# USB_PD.net
KiCad netlist of a schematic drawn in Altium Designer
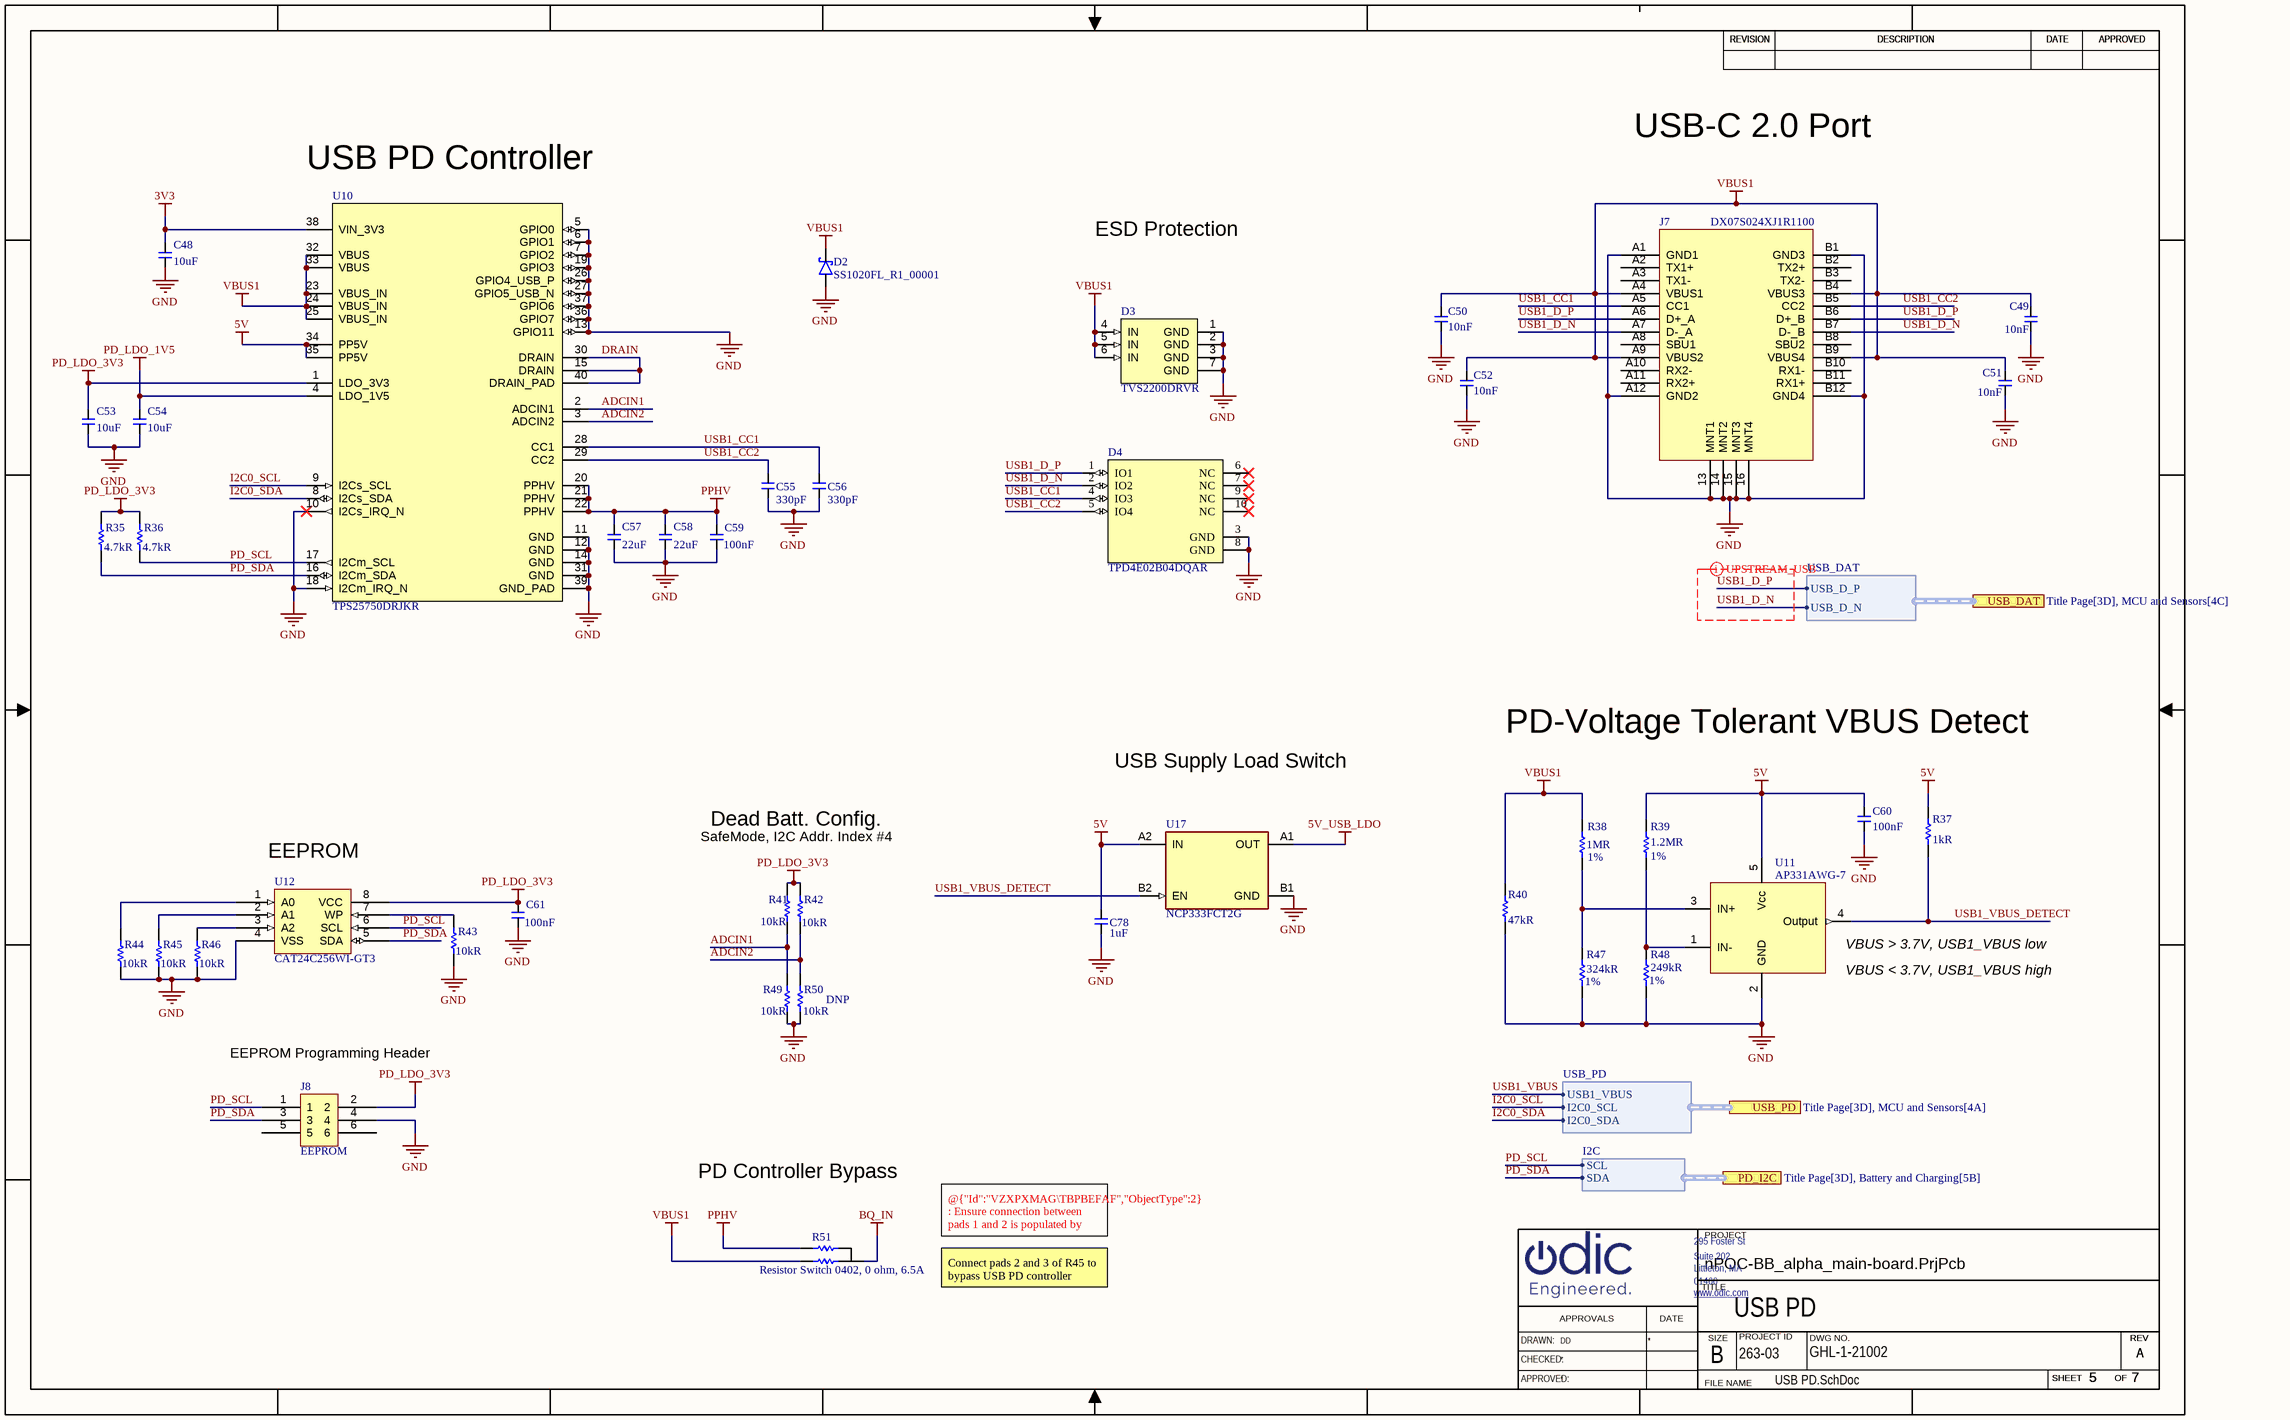
[diagram p0: USB PD.SchDoc]

(export (version "E")
  (design (tool "Eeschema 10.0.6"))
  (components
    (comp (ref "C48")
      (value "C0402_10u_10V_20pct")
      (footprint "C0402")
      (description "Ceramic capacitor SMD; 0402; 10uF; 10V; X5R; 20%")
      (fields (field (name "CAPACITANCE") "10uF") (field (name "TOLERANCE") "20%"))
      (libsource (lib "Odic Inc") (part "cAP"))
    )
    (comp (ref "C49")
      (value "10nF")
      (footprint "C0402")
      (description "Multilayer Ceramic Capacitor, 0.01 uF, 35 V, ± 10%, X7R, 0402 [1005 Metric]")
      (fields (field (name "TOLERANCE") "10%") (field (name "Comment") "C0402_10n_35V_10pct"))
      (libsource (lib "Odic Inc") (part "cAP"))
    )
    (comp (ref "C50")
      (value "10nF")
      (footprint "C0402")
      (description "Multilayer Ceramic Capacitor, 0.01 uF, 35 V, ± 10%, X7R, 0402 [1005 Metric]")
      (fields (field (name "TOLERANCE") "10%") (field (name "Comment") "C0402_10n_35V_10pct"))
      (libsource (lib "Odic Inc") (part "cAP"))
    )
    (comp (ref "C51")
      (value "10nF")
      (footprint "C0402")
      (description "Multilayer Ceramic Capacitor, 0.01 uF, 35 V, ± 10%, X7R, 0402 [1005 Metric]")
      (fields (field (name "TOLERANCE") "10%") (field (name "Comment") "C0402_10n_35V_10pct"))
      (libsource (lib "Odic Inc") (part "cAP"))
    )
    (comp (ref "C52")
      (value "10nF")
      (footprint "C0402")
      (description "Multilayer Ceramic Capacitor, 0.01 uF, 35 V, ± 10%, X7R, 0402 [1005 Metric]")
      (fields (field (name "TOLERANCE") "10%") (field (name "Comment") "C0402_10n_35V_10pct"))
      (libsource (lib "Odic Inc") (part "cAP"))
    )
    (comp (ref "C53")
      (value "C0402_10u_10V_20pct")
      (footprint "C0402")
      (description "Ceramic capacitor SMD; 0402; 10uF; 10V; X5R; 20%")
      (fields (field (name "CAPACITANCE") "10uF") (field (name "TOLERANCE") "20%"))
      (libsource (lib "Odic Inc") (part "cAP"))
    )
    (comp (ref "C54")
      (value "C0402_10u_10V_20pct")
      (footprint "C0402")
      (description "Ceramic capacitor SMD; 0402; 10uF; 10V; X5R; 20%")
      (fields (field (name "CAPACITANCE") "10uF") (field (name "TOLERANCE") "20%"))
      (libsource (lib "Odic Inc") (part "cAP"))
    )
    (comp (ref "C55")
      (value "330pF")
      (footprint "C0402")
      (description "0402 330 pF 50 V ±5% Tolerance C0G SMT Multilayer Ceramic Capacitor")
      (fields (field (name "VOLTAGE") "50V") (field (name "TOLERANCE") "5%"))
      (libsource (lib "Odic Inc") (part "cAP"))
    )
    (comp (ref "C56")
      (value "330pF")
      (footprint "C0402")
      (description "0402 330 pF 50 V ±5% Tolerance C0G SMT Multilayer Ceramic Capacitor")
      (fields (field (name "VOLTAGE") "50V") (field (name "TOLERANCE") "5%"))
      (libsource (lib "Odic Inc") (part "cAP"))
    )
    (comp (ref "C57")
      (value "C0805_22u_25V_20pct")
      (footprint "c0805")
      (description "Multilayer Ceramic Capacitor, 22 uF, 25 V, ± 20%, X5R, 0805 [2012 Metric]")
      (fields (field (name "CAPACITANCE") "22uF"))
      (libsource (lib "Odic Inc") (part "cAP"))
    )
    (comp (ref "C58")
      (value "C0805_22u_25V_20pct")
      (footprint "c0805")
      (description "Multilayer Ceramic Capacitor, 22 uF, 25 V, ± 20%, X5R, 0805 [2012 Metric]")
      (fields (field (name "CAPACITANCE") "22uF"))
      (libsource (lib "Odic Inc") (part "cAP"))
    )
    (comp (ref "C59")
      (value "C0402_0u1_25V_10pct")
      (footprint "C0402")
      (description "Cap Ceramic 0.1uF 25V X5R 10% Pad SMD 0402 Multi Layer Ceramic Capacitor (MLCC)")
      (fields
        (field (name "VOLTAGE") "25V")
        (field (name "TOLERANCE") "10%")
        (field (name "CAPACITANCE") "100nF")
      )
      (libsource (lib "Odic Inc") (part "cAP"))
    )
    (comp (ref "C60")
      (value "C0402_100n_16V_10pct")
      (footprint "C0402")
      (description "0.1 µF ±10% 16V Ceramic Capacitor X7R 0402 (1005 Metric)")
      (fields
        (field (name "VOLTAGE") "16V")
        (field (name "TOLERANCE") "10%")
        (field (name "CAPACITANCE") "100nF")
      )
      (libsource (lib "Odic Inc") (part "cAP"))
    )
    (comp (ref "C61")
      (value "C0402_0u1_25V_10pct")
      (footprint "C0402")
      (description "Cap Ceramic 0.1uF 25V X5R 10% Pad SMD 0402 Multi Layer Ceramic Capacitor (MLCC)")
      (fields
        (field (name "VOLTAGE") "25V")
        (field (name "TOLERANCE") "10%")
        (field (name "CAPACITANCE") "100nF")
      )
      (libsource (lib "Odic Inc") (part "cAP"))
    )
    (comp (ref "C78")
      (value "C0402_1u_6V3_10pct")
      (footprint "C0402")
      (description "Cap Ceramic 1uF 6.3V X5R 10% SMD 0402 85C Paper T/R")
      (fields (field (name "CAPACITANCE") "1uF") (field (name "TOLERANCE") "10%"))
      (libsource (lib "Odic Inc") (part "cAP"))
    )
    (comp (ref "D2")
      (value "SS1020FL_R1_00001")
      (footprint "sod-123fl_AK")
      (description "Diode Schottky 20V 1A 2-Pin SOD-123FL T/R")
      (libsource (lib "Odic Inc") (part "Schottky"))
    )
    (comp (ref "D3")
      (value "TVS2200DRVR")
      (footprint "dfn7_2x2_p65mm")
      (description "22-V flat-clamp surge protection device 6-WSON -40 to 125")
      (libsource (lib "Odic Inc") (part "TVS2200DRVR-sym"))
    )
    (comp (ref "D4")
      (value "TPD4E02B04DQAR")
      (footprint "dfn10_1p1x2p6_p5mm")
      (description "Quad 0.25-pF, ±3.6-V, ±12-kV ESD protection diode for USB 3.0, HDMI 2.0 & High Speed Signals")
      (libsource (lib "Odic Inc") (part "TPD4E02B04DQAR-sym"))
    )
    (comp (ref "J7")
      (value "DX07S024XJ1R1100")
      (footprint "USB_JAE_DX07S024XJ1R1100")
      (libsource (lib "Odic Inc") (part "DX07S024XJ1R1100-symbol-1"))
    )
    (comp (ref "J8")
      (value "EEPROM")
      (footprint "tc2030-mcp-nl")
      (description "6 Pin Tag-Connect Header Footprint. Pads.")
      (libsource (lib "Odic Inc") (part "TC2030-FP-Symbol-1"))
    )
    (comp (ref "R35")
      (value "R0402_4k7_1pct")
      (footprint "R0402")
      (description "RES 4.7K OHM 1% 1/16W 0402")
      (fields (field (name "TOLERANCE") "1%") (field (name "RESISTANCE") "4.7kR"))
      (libsource (lib "Odic Inc") (part "RES"))
    )
    (comp (ref "R36")
      (value "R0402_4k7_1pct")
      (footprint "R0402")
      (description "RES 4.7K OHM 1% 1/16W 0402")
      (fields (field (name "TOLERANCE") "1%") (field (name "RESISTANCE") "4.7kR"))
      (libsource (lib "Odic Inc") (part "RES"))
    )
    (comp (ref "R37")
      (value "R0402_1k0_1pct")
      (footprint "R0402")
      (description "Surface Mount Chip Resistor, Thick Film, RC Series, 1 kohm, 62.5 mW, 1%, 50 V, 0402 [1005 Metric]")
      (fields (field (name "RESISTANCE") "1kR") (field (name "TOLERANCE") "1%"))
      (libsource (lib "Odic Inc") (part "RES"))
    )
    (comp (ref "R38")
      (value "1MR")
      (footprint "R0402")
      (description "Res Thick Film 0402 1M Ohm 1% 0.063W(1/16W) ±100ppm/C Pad SMD T/R")
      (fields (field (name "TOLERANCE") "1%") (field (name "Comment") "R0402_1M_1pct"))
      (libsource (lib "Odic Inc") (part "RES"))
    )
    (comp (ref "R39")
      (value "R0402_1M2_1pct")
      (footprint "R0402")
      (description "Res Thick Film 0402 1.2M Ohm 1% 0.063W(1/16W) ±100ppm/C Pad SMD Automotive T/R")
      (fields (field (name "RESISTANCE") "1.2MR") (field (name "TOLERANCE") "1%"))
      (libsource (lib "Odic Inc") (part "RES"))
    )
    (comp (ref "R40")
      (value "R0402_47k_1pct")
      (footprint "R0402")
      (description "Res General Purpose Thick Film 0402 47K Ohm 1% 1/16W ±100ppm/°C Molded SMD Paper T/R")
      (fields (field (name "TOLERANCE") "1%") (field (name "RESISTANCE") "47kR"))
      (libsource (lib "Odic Inc") (part "RES"))
    )
    (comp (ref "R41")
      (value "R0402_10k_1pct")
      (footprint "R0402")
      (description "Res Thick Film 0402 10K Ohm 1% 1/16W ±100ppm/°C Molded SMD SMD T/R")
      (fields (field (name "RESISTANCE") "10kR") (field (name "TOLERANCE") "1%"))
      (libsource (lib "Odic Inc") (part "RES"))
    )
    (comp (ref "R42")
      (value "R0402_10k_1pct")
      (footprint "R0402")
      (description "Res Thick Film 0402 10K Ohm 1% 1/16W ±100ppm/°C Molded SMD SMD T/R")
      (fields (field (name "RESISTANCE") "10kR") (field (name "TOLERANCE") "1%"))
      (libsource (lib "Odic Inc") (part "RES"))
    )
    (comp (ref "R43")
      (value "R0402_10k_1pct")
      (footprint "R0402")
      (description "Res Thick Film 0402 10K Ohm 1% 1/16W ±100ppm/°C Molded SMD SMD T/R")
      (fields (field (name "RESISTANCE") "10kR") (field (name "TOLERANCE") "1%"))
      (libsource (lib "Odic Inc") (part "RES"))
    )
    (comp (ref "R44")
      (value "R0402_10k_1pct")
      (footprint "R0402")
      (description "Res Thick Film 0402 10K Ohm 1% 1/16W ±100ppm/°C Molded SMD SMD T/R")
      (fields (field (name "RESISTANCE") "10kR") (field (name "TOLERANCE") "1%"))
      (libsource (lib "Odic Inc") (part "RES"))
    )
    (comp (ref "R45")
      (value "R0402_10k_1pct")
      (footprint "R0402")
      (description "Res Thick Film 0402 10K Ohm 1% 1/16W ±100ppm/°C Molded SMD SMD T/R")
      (fields (field (name "RESISTANCE") "10kR") (field (name "TOLERANCE") "1%"))
      (libsource (lib "Odic Inc") (part "RES"))
    )
    (comp (ref "R46")
      (value "R0402_10k_1pct")
      (footprint "R0402")
      (description "Res Thick Film 0402 10K Ohm 1% 1/16W ±100ppm/°C Molded SMD SMD T/R")
      (fields (field (name "RESISTANCE") "10kR") (field (name "TOLERANCE") "1%"))
      (libsource (lib "Odic Inc") (part "RES"))
    )
    (comp (ref "R47")
      (value "324kR")
      (footprint "R0402")
      (description "SMD Chip Resistor, 324 kOhm, ± 1%, 63 mW, 0402 [1005 Metric], Thick Film, General Purpose")
      (fields (field (name "TOLERANCE") "1%") (field (name "Comment") "R0402_324k_1pct"))
      (libsource (lib "Odic Inc") (part "RES"))
    )
    (comp (ref "R48")
      (value "R0402_249k_1pct")
      (footprint "R0402")
      (description "Res Thick Film 0402 249K Ohm 1% 0.063W ±100ppm/°C Molded SMD Paper T/R")
      (fields (field (name "TOLERANCE") "1%") (field (name "RESISTANCE") "249kR"))
      (libsource (lib "Odic Inc") (part "RES"))
    )
    (comp (ref "R49")
      (value "R0402_10k_1pct")
      (footprint "R0402")
      (description "Res Thick Film 0402 10K Ohm 1% 1/16W ±100ppm/°C Molded SMD SMD T/R")
      (fields (field (name "RESISTANCE") "10kR") (field (name "TOLERANCE") "1%"))
      (libsource (lib "Odic Inc") (part "RES"))
    )
    (comp (ref "R50")
      (value "R0402_10k_1pct")
      (footprint "R0402")
      (description "Res Thick Film 0402 10K Ohm 1% 1/16W ±100ppm/°C Molded SMD SMD T/R")
      (fields
        (field (name "RESISTANCE") "10kR")
        (field (name "TOLERANCE") "1%")
        (field (name "INSTALL") "DNP")
      )
      (libsource (lib "Odic Inc") (part "RES"))
    )
    (comp (ref "R51")
      (value "Resistor Switch 0402, 0 ohm, 6.5A")
      (footprint "r0402x2")
      (fields (field (name "TOLERANCE") "5%"))
      (libsource (lib "Odic Inc") (part "RES_SWITCH"))
    )
    (comp (ref "U10")
      (value "TPS25750DRJKR")
      (footprint "qfn40_6x4_p4mm-RJK0038B")
      (description "Highly integrated USB Type-C® and USB PD controller with pre-configured GUI 38-WQFN -40 to 125")
      (libsource (lib "Odic Inc") (part "TPS25750DRJKR-Symbol-1"))
    )
    (comp (ref "U11")
      (value "AP331AWG-7")
      (footprint "SOT25")
      (description "IC COMPARATOR SGL DIFF SOT-25")
      (libsource (lib "Odic Inc") (part "84157f6d693ce6938d681314262b7f3"))
    )
    (comp (ref "U12")
      (value "CAT24C256WI-GT3")
      (footprint "SO8")
      (description "IC EEPROM 256KBIT 400KHZ 8SOIC")
      (libsource (lib "Odic Inc") (part "CAT24C256WI-GT3-Symbol-1"))
    )
    (comp (ref "U17")
      (value "NCP333FCT2G")
      (footprint "bga4_p743xp743_p4mm")
      (description "IC LOAD SWITCH W/DIS 1.5A 4WLCSP")
      (libsource (lib "Odic Inc") (part "97019fd276bc7644be76e1f711e9589"))
    )
  )
  (nets
    (net (code "4") (name "/ADCIN1") (class "Default")
      (node (ref "R41") (pin "1") (pinfunction "1_1") (pintype "passive"))
      (node (ref "R49") (pin "2") (pinfunction "2_2") (pintype "passive"))
      (node (ref "U10") (pin "2") (pinfunction "ADCIN1_2") (pintype "passive"))
    )
    (net (code "5") (name "/ADCIN2") (class "Default")
      (node (ref "R42") (pin "1") (pinfunction "1_1") (pintype "passive"))
      (node (ref "R50") (pin "2") (pinfunction "2_2") (pintype "passive"))
      (node (ref "U10") (pin "3") (pinfunction "ADCIN2_3") (pintype "passive"))
    )
    (net (code "6") (name "/DRAIN") (class "Default")
      (node (ref "U10") (pin "15") (pinfunction "DRAIN_15") (pintype "passive"))
      (node (ref "U10") (pin "30") (pinfunction "DRAIN_30") (pintype "passive"))
      (node (ref "U10") (pin "40") (pinfunction "DRAIN_PAD_40") (pintype "passive"))
    )
    (net (code "7") (name "/I2C0_SCL") (class "Default")
      (node (ref "U10") (pin "9") (pinfunction "I2Cs_SCL_9") (pintype "input"))
    )
    (net (code "8") (name "/I2C0_SDA") (class "Default")
      (node (ref "U10") (pin "8") (pinfunction "I2Cs_SDA_8") (pintype "bidirectional"))
    )
    (net (code "9") (name "/PD_SCL") (class "Default")
      (node (ref "J8") (pin "1") (pinfunction "1_1") (pintype "passive"))
      (node (ref "R36") (pin "1") (pinfunction "1_1") (pintype "passive"))
      (node (ref "U10") (pin "17") (pinfunction "I2Cm_SCL_17") (pintype "output"))
      (node (ref "U12") (pin "6") (pinfunction "SCL_6") (pintype "input"))
    )
    (net (code "10") (name "/PD_SDA") (class "Default")
      (node (ref "J8") (pin "3") (pinfunction "3_3") (pintype "passive"))
      (node (ref "R35") (pin "1") (pinfunction "1_1") (pintype "passive"))
      (node (ref "U10") (pin "16") (pinfunction "I2Cm_SDA_16") (pintype "bidirectional"))
      (node (ref "U12") (pin "5") (pinfunction "SDA_5") (pintype "bidirectional"))
    )
    (net (code "11") (name "/USB1_CC1") (class "Default")
      (node (ref "C56") (pin "2") (pinfunction "2_2") (pintype "passive"))
      (node (ref "D4") (pin "4") (pinfunction "IO3_4") (pintype "bidirectional"))
      (node (ref "J7") (pin "A5") (pinfunction "CC1_A5") (pintype "passive"))
      (node (ref "U10") (pin "28") (pinfunction "CC1_28") (pintype "passive"))
    )
    (net (code "12") (name "/USB1_CC2") (class "Default")
      (node (ref "C55") (pin "2") (pinfunction "2_2") (pintype "passive"))
      (node (ref "D4") (pin "5") (pinfunction "IO4_5") (pintype "bidirectional"))
      (node (ref "J7") (pin "B5") (pinfunction "CC2_B5") (pintype "passive"))
      (node (ref "U10") (pin "29") (pinfunction "CC2_29") (pintype "passive"))
    )
    (net (code "13") (name "/USB1_D_N") (class "Default")
      (node (ref "D4") (pin "2") (pinfunction "IO2_2") (pintype "bidirectional"))
      (node (ref "J7") (pin "A7") (pinfunction "D-_A_A7") (pintype "passive"))
      (node (ref "J7") (pin "B7") (pinfunction "D-_B_B7") (pintype "passive"))
    )
    (net (code "14") (name "/USB1_D_P") (class "Default")
      (node (ref "D4") (pin "1") (pinfunction "IO1_1") (pintype "bidirectional"))
      (node (ref "J7") (pin "A6") (pinfunction "D+_A_A6") (pintype "passive"))
      (node (ref "J7") (pin "B6") (pinfunction "D+_B_B6") (pintype "passive"))
    )
    (net (code "16") (name "/USB1_VBUS_DETECT") (class "Default")
      (node (ref "R37") (pin "1") (pinfunction "1_1") (pintype "passive"))
      (node (ref "U11") (pin "4") (pinfunction "Output_4") (pintype "output"))
      (node (ref "U17") (pin "B2") (pinfunction "EN_B2") (pintype "input"))
    )
    (net (code "20") (name "3V3") (class "Default")
      (node (ref "C48") (pin "2") (pinfunction "2_2") (pintype "passive"))
      (node (ref "U10") (pin "38") (pinfunction "VIN_3V3_38") (pintype "power_in"))
    )
    (net (code "21") (name "5V") (class "Default")
      (node (ref "C60") (pin "2") (pinfunction "2_2") (pintype "passive"))
      (node (ref "C78") (pin "2") (pinfunction "2_2") (pintype "passive"))
      (node (ref "R37") (pin "2") (pinfunction "2_2") (pintype "passive"))
      (node (ref "R39") (pin "2") (pinfunction "2_2") (pintype "passive"))
      (node (ref "U10") (pin "34") (pinfunction "PP5V_34") (pintype "power_in"))
      (node (ref "U10") (pin "35") (pinfunction "PP5V_35") (pintype "power_in"))
      (node (ref "U11") (pin "5") (pinfunction "Vcc_5") (pintype "power_in"))
      (node (ref "U17") (pin "A2") (pinfunction "IN_A2") (pintype "power_in"))
    )
    (net (code "22") (name "5V_USB_LDO") (class "Default")
      (node (ref "U17") (pin "A1") (pinfunction "OUT_A1") (pintype "power_in"))
    )
    (net (code "23") (name "BQ_IN") (class "Default")
      (node (ref "R51") (pin "2") (pinfunction "2_2") (pintype "passive"))
    )
    (net (code "24") (name "GND") (class "Default")
      (node (ref "C48") (pin "1") (pinfunction "1_1") (pintype "passive"))
      (node (ref "C49") (pin "1") (pinfunction "1_1") (pintype "passive"))
      (node (ref "C50") (pin "1") (pinfunction "1_1") (pintype "passive"))
      (node (ref "C51") (pin "1") (pinfunction "1_1") (pintype "passive"))
      (node (ref "C52") (pin "1") (pinfunction "1_1") (pintype "passive"))
      (node (ref "C53") (pin "1") (pinfunction "1_1") (pintype "passive"))
      (node (ref "C54") (pin "1") (pinfunction "1_1") (pintype "passive"))
      (node (ref "C55") (pin "1") (pinfunction "1_1") (pintype "passive"))
      (node (ref "C56") (pin "1") (pinfunction "1_1") (pintype "passive"))
      (node (ref "C57") (pin "1") (pinfunction "1_1") (pintype "passive"))
      (node (ref "C58") (pin "1") (pinfunction "1_1") (pintype "passive"))
      (node (ref "C59") (pin "1") (pinfunction "1_1") (pintype "passive"))
      (node (ref "C60") (pin "1") (pinfunction "1_1") (pintype "passive"))
      (node (ref "C61") (pin "1") (pinfunction "1_1") (pintype "passive"))
      (node (ref "C78") (pin "1") (pinfunction "1_1") (pintype "passive"))
      (node (ref "D2") (pin "A") (pinfunction "A_A") (pintype "passive"))
      (node (ref "D3") (pin "1") (pinfunction "GND_1") (pintype "power_in"))
      (node (ref "D3") (pin "2") (pinfunction "GND_2") (pintype "power_in"))
      (node (ref "D3") (pin "3") (pinfunction "GND_3") (pintype "power_in"))
      (node (ref "D3") (pin "7") (pinfunction "GND_7") (pintype "power_in"))
      (node (ref "D4") (pin "3") (pinfunction "GND_3") (pintype "power_in"))
      (node (ref "D4") (pin "8") (pinfunction "GND_8") (pintype "power_in"))
      (node (ref "J7") (pin "13") (pinfunction "MNT1_13") (pintype "passive"))
      (node (ref "J7") (pin "14") (pinfunction "MNT2_14") (pintype "passive"))
      (node (ref "J7") (pin "15") (pinfunction "MNT3_15") (pintype "passive"))
      (node (ref "J7") (pin "16") (pinfunction "MNT4_16") (pintype "passive"))
      (node (ref "J7") (pin "A1") (pinfunction "GND1_A1") (pintype "passive"))
      (node (ref "J7") (pin "A12") (pinfunction "GND2_A12") (pintype "passive"))
      (node (ref "J7") (pin "B1") (pinfunction "GND3_B1") (pintype "passive"))
      (node (ref "J7") (pin "B12") (pinfunction "GND4_B12") (pintype "passive"))
      (node (ref "J8") (pin "4") (pinfunction "4_4") (pintype "passive"))
      (node (ref "R40") (pin "1") (pinfunction "1_1") (pintype "passive"))
      (node (ref "R43") (pin "1") (pinfunction "1_1") (pintype "passive"))
      (node (ref "R44") (pin "1") (pinfunction "1_1") (pintype "passive"))
      (node (ref "R45") (pin "1") (pinfunction "1_1") (pintype "passive"))
      (node (ref "R46") (pin "1") (pinfunction "1_1") (pintype "passive"))
      (node (ref "R47") (pin "1") (pinfunction "1_1") (pintype "passive"))
      (node (ref "R48") (pin "1") (pinfunction "1_1") (pintype "passive"))
      (node (ref "R49") (pin "1") (pinfunction "1_1") (pintype "passive"))
      (node (ref "R50") (pin "1") (pinfunction "1_1") (pintype "passive"))
      (node (ref "U10") (pin "10") (pinfunction "I2Cs_IRQ_N_10") (pintype "output"))
      (node (ref "U10") (pin "11") (pinfunction "GND_11") (pintype "power_in"))
      (node (ref "U10") (pin "12") (pinfunction "GND_12") (pintype "power_in"))
      (node (ref "U10") (pin "13") (pinfunction "GPIO11_13") (pintype "bidirectional"))
      (node (ref "U10") (pin "14") (pinfunction "GND_14") (pintype "power_in"))
      (node (ref "U10") (pin "18") (pinfunction "I2Cm_IRQ_N_18") (pintype "input"))
      (node (ref "U10") (pin "19") (pinfunction "GPIO3_19") (pintype "bidirectional"))
      (node (ref "U10") (pin "26") (pinfunction "GPIO4_USB_P_26") (pintype "bidirectional"))
      (node (ref "U10") (pin "27") (pinfunction "GPIO5_USB_N_27") (pintype "bidirectional"))
      (node (ref "U10") (pin "31") (pinfunction "GND_31") (pintype "power_in"))
      (node (ref "U10") (pin "36") (pinfunction "GPIO7_36") (pintype "bidirectional"))
      (node (ref "U10") (pin "37") (pinfunction "GPIO6_37") (pintype "bidirectional"))
      (node (ref "U10") (pin "39") (pinfunction "GND_PAD_39") (pintype "power_in"))
      (node (ref "U10") (pin "5") (pinfunction "GPIO0_5") (pintype "bidirectional"))
      (node (ref "U10") (pin "6") (pinfunction "GPIO1_6") (pintype "bidirectional"))
      (node (ref "U10") (pin "7") (pinfunction "GPIO2_7") (pintype "bidirectional"))
      (node (ref "U11") (pin "2") (pinfunction "GND_2") (pintype "power_in"))
      (node (ref "U12") (pin "4") (pinfunction "VSS_4") (pintype "passive"))
      (node (ref "U17") (pin "B1") (pinfunction "GND_B1") (pintype "power_in"))
    )
    (net (code "25") (name "Net-(U11-IN+)") (class "Default")
      (node (ref "R38") (pin "1") (pinfunction "1_1") (pintype "passive"))
      (node (ref "R47") (pin "2") (pinfunction "2_2") (pintype "passive"))
      (node (ref "U11") (pin "3") (pinfunction "IN+_3") (pintype "tri_state"))
    )
    (net (code "26") (name "Net-(U11-IN-)") (class "Default")
      (node (ref "R39") (pin "1") (pinfunction "1_1") (pintype "passive"))
      (node (ref "R48") (pin "2") (pinfunction "2_2") (pintype "passive"))
      (node (ref "U11") (pin "1") (pinfunction "IN-_1") (pintype "tri_state"))
    )
    (net (code "27") (name "Net-(U12-A0)") (class "Default")
      (node (ref "R44") (pin "2") (pinfunction "2_2") (pintype "passive"))
      (node (ref "U12") (pin "1") (pinfunction "A0_1") (pintype "input"))
    )
    (net (code "28") (name "Net-(U12-A1)") (class "Default")
      (node (ref "R45") (pin "2") (pinfunction "2_2") (pintype "passive"))
      (node (ref "U12") (pin "2") (pinfunction "A1_2") (pintype "input"))
    )
    (net (code "29") (name "Net-(U12-A2)") (class "Default")
      (node (ref "R46") (pin "2") (pinfunction "2_2") (pintype "passive"))
      (node (ref "U12") (pin "3") (pinfunction "A2_3") (pintype "input"))
    )
    (net (code "30") (name "Net-(U12-WP)") (class "Default")
      (node (ref "R43") (pin "2") (pinfunction "2_2") (pintype "passive"))
      (node (ref "U12") (pin "7") (pinfunction "WP_7") (pintype "input"))
    )
    (net (code "31") (name "PD_LDO_1V5") (class "Default")
      (node (ref "C54") (pin "2") (pinfunction "2_2") (pintype "passive"))
      (node (ref "U10") (pin "4") (pinfunction "LDO_1V5_4") (pintype "passive"))
    )
    (net (code "32") (name "PD_LDO_3V3") (class "Default")
      (node (ref "C53") (pin "2") (pinfunction "2_2") (pintype "passive"))
      (node (ref "C61") (pin "2") (pinfunction "2_2") (pintype "passive"))
      (node (ref "J8") (pin "2") (pinfunction "2_2") (pintype "passive"))
      (node (ref "R35") (pin "2") (pinfunction "2_2") (pintype "passive"))
      (node (ref "R36") (pin "2") (pinfunction "2_2") (pintype "passive"))
      (node (ref "R41") (pin "2") (pinfunction "2_2") (pintype "passive"))
      (node (ref "R42") (pin "2") (pinfunction "2_2") (pintype "passive"))
      (node (ref "U10") (pin "1") (pinfunction "LDO_3V3_1") (pintype "passive"))
      (node (ref "U12") (pin "8") (pinfunction "VCC_8") (pintype "passive"))
    )
    (net (code "33") (name "PPHV") (class "Default")
      (node (ref "C57") (pin "2") (pinfunction "2_2") (pintype "passive"))
      (node (ref "C58") (pin "2") (pinfunction "2_2") (pintype "passive"))
      (node (ref "C59") (pin "2") (pinfunction "2_2") (pintype "passive"))
      (node (ref "R51") (pin "1") (pinfunction "1_1") (pintype "passive"))
      (node (ref "U10") (pin "20") (pinfunction "PPHV_20") (pintype "passive"))
      (node (ref "U10") (pin "21") (pinfunction "PPHV_21") (pintype "passive"))
      (node (ref "U10") (pin "22") (pinfunction "PPHV_22") (pintype "passive"))
    )
    (net (code "34") (name "VBUS1") (class "Default")
      (node (ref "C49") (pin "2") (pinfunction "2_2") (pintype "passive"))
      (node (ref "C50") (pin "2") (pinfunction "2_2") (pintype "passive"))
      (node (ref "C51") (pin "2") (pinfunction "2_2") (pintype "passive"))
      (node (ref "C52") (pin "2") (pinfunction "2_2") (pintype "passive"))
      (node (ref "D2") (pin "K") (pinfunction "K_K") (pintype "passive"))
      (node (ref "D3") (pin "4") (pinfunction "IN_4") (pintype "input"))
      (node (ref "D3") (pin "5") (pinfunction "IN_5") (pintype "input"))
      (node (ref "D3") (pin "6") (pinfunction "IN_6") (pintype "input"))
      (node (ref "J7") (pin "A4") (pinfunction "VBUS1_A4") (pintype "passive"))
      (node (ref "J7") (pin "A9") (pinfunction "VBUS2_A9") (pintype "passive"))
      (node (ref "J7") (pin "B4") (pinfunction "VBUS3_B4") (pintype "passive"))
      (node (ref "J7") (pin "B9") (pinfunction "VBUS4_B9") (pintype "passive"))
      (node (ref "R38") (pin "2") (pinfunction "2_2") (pintype "passive"))
      (node (ref "R40") (pin "2") (pinfunction "2_2") (pintype "passive"))
      (node (ref "R51") (pin "3") (pinfunction "3_3") (pintype "passive"))
      (node (ref "U10") (pin "23") (pinfunction "VBUS_IN_23") (pintype "power_in"))
      (node (ref "U10") (pin "24") (pinfunction "VBUS_IN_24") (pintype "power_in"))
      (node (ref "U10") (pin "25") (pinfunction "VBUS_IN_25") (pintype "power_in"))
      (node (ref "U10") (pin "32") (pinfunction "VBUS_32") (pintype "power_in"))
      (node (ref "U10") (pin "33") (pinfunction "VBUS_33") (pintype "power_in"))
    )
    (net (code "35") (name "unconnected-(D4-NC-Pad6)") (class "Default")
      (node (ref "D4") (pin "6") (pinfunction "NC_6") (pintype "passive+no_connect"))
    )
    (net (code "36") (name "unconnected-(D4-NC-Pad7)") (class "Default")
      (node (ref "D4") (pin "7") (pinfunction "NC_7") (pintype "passive+no_connect"))
    )
    (net (code "37") (name "unconnected-(D4-NC-Pad9)") (class "Default")
      (node (ref "D4") (pin "9") (pinfunction "NC_9") (pintype "passive+no_connect"))
    )
    (net (code "38") (name "unconnected-(D4-NC-Pad10)") (class "Default")
      (node (ref "D4") (pin "10") (pinfunction "NC_10") (pintype "passive+no_connect"))
    )
    (net (code "39") (name "unconnected-(J7-RX1+-PadB11)") (class "Default")
      (node (ref "J7") (pin "B11") (pinfunction "RX1+_B11") (pintype "passive"))
    )
    (net (code "40") (name "unconnected-(J7-RX1--PadB10)") (class "Default")
      (node (ref "J7") (pin "B10") (pinfunction "RX1-_B10") (pintype "passive"))
    )
    (net (code "41") (name "unconnected-(J7-RX2+-PadA11)") (class "Default")
      (node (ref "J7") (pin "A11") (pinfunction "RX2+_A11") (pintype "passive"))
    )
    (net (code "42") (name "unconnected-(J7-RX2--PadA10)") (class "Default")
      (node (ref "J7") (pin "A10") (pinfunction "RX2-_A10") (pintype "passive"))
    )
    (net (code "43") (name "unconnected-(J7-SBU1-PadA8)") (class "Default")
      (node (ref "J7") (pin "A8") (pinfunction "SBU1_A8") (pintype "passive"))
    )
    (net (code "44") (name "unconnected-(J7-SBU2-PadB8)") (class "Default")
      (node (ref "J7") (pin "B8") (pinfunction "SBU2_B8") (pintype "passive"))
    )
    (net (code "45") (name "unconnected-(J7-TX1+-PadA2)") (class "Default")
      (node (ref "J7") (pin "A2") (pinfunction "TX1+_A2") (pintype "passive"))
    )
    (net (code "46") (name "unconnected-(J7-TX1--PadA3)") (class "Default")
      (node (ref "J7") (pin "A3") (pinfunction "TX1-_A3") (pintype "passive"))
    )
    (net (code "47") (name "unconnected-(J7-TX2+-PadB2)") (class "Default")
      (node (ref "J7") (pin "B2") (pinfunction "TX2+_B2") (pintype "passive"))
    )
    (net (code "48") (name "unconnected-(J7-TX2--PadB3)") (class "Default")
      (node (ref "J7") (pin "B3") (pinfunction "TX2-_B3") (pintype "passive"))
    )
    (net (code "49") (name "unconnected-(J8-Pad5)") (class "Default")
      (node (ref "J8") (pin "5") (pinfunction "5_5") (pintype "passive"))
    )
    (net (code "50") (name "unconnected-(J8-Pad6)") (class "Default")
      (node (ref "J8") (pin "6") (pinfunction "6_6") (pintype "passive"))
    )
  )
)
